# timer_rele.net
KiCad netlist of a schematic drawn in EAGLE
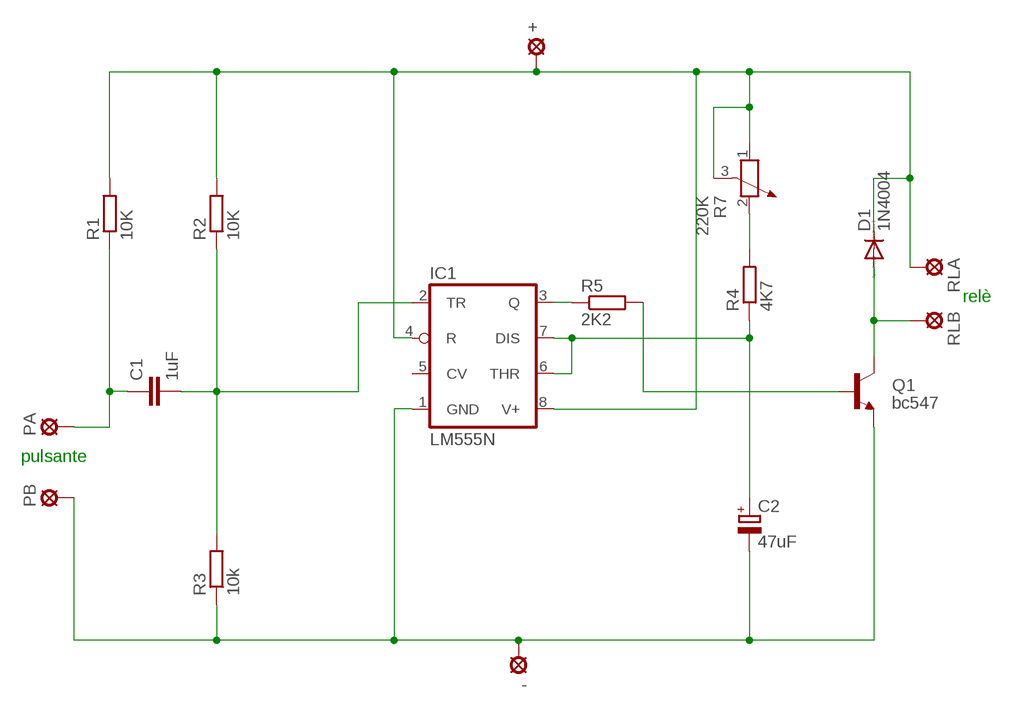
[diagram p0: schematic, sheet 1]

(export (version "E")
  (design (tool "Eeschema 10.0.6"))
  (components
    (comp (ref "+")
      (value "LSP10")
      (footprint "eagle-import:LSP10")
      (libsource (lib "eagle-import") (part "LSP10"))
    )
    (comp (ref "-")
      (value "LSP10")
      (footprint "eagle-import:LSP10")
      (libsource (lib "eagle-import") (part "LSP10"))
    )
    (comp (ref "C1")
      (value "1uF")
      (footprint "eagle-import:C050-030X075")
      (libsource (lib "eagle-import") (part "C-EU050-030X075"))
    )
    (comp (ref "C2")
      (value "47uF")
      (footprint "eagle-import:E2-5")
      (libsource (lib "eagle-import") (part "CPOL-EUE2-5"))
    )
    (comp (ref "D1")
      (value "1N4004")
      (footprint "eagle-import:DO41-10")
      (libsource (lib "eagle-import") (part "1N4004"))
    )
    (comp (ref "IC1")
      (value "LM555N")
      (footprint "eagle-import:DIL08")
      (libsource (lib "eagle-import") (part "555NLM"))
    )
    (comp (ref "PA")
      (value "LSP10")
      (footprint "eagle-import:LSP10")
      (libsource (lib "eagle-import") (part "LSP10"))
    )
    (comp (ref "PB")
      (value "LSP10")
      (footprint "eagle-import:LSP10")
      (libsource (lib "eagle-import") (part "LSP10"))
    )
    (comp (ref "Q1")
      (value "bc547")
      (footprint "eagle-import:TO-92-AMMO")
      (libsource (lib "eagle-import") (part "TRANSISTOR_NPNBC547"))
    )
    (comp (ref "R1")
      (value "10K")
      (footprint "eagle-import:0207_10")
      (libsource (lib "eagle-import") (part "R-EU_0207/10"))
    )
    (comp (ref "R2")
      (value "10K")
      (footprint "eagle-import:0207_10")
      (libsource (lib "eagle-import") (part "R-EU_0207/10"))
    )
    (comp (ref "R3")
      (value "10k")
      (footprint "eagle-import:0207_10")
      (libsource (lib "eagle-import") (part "R-EU_0207/10"))
    )
    (comp (ref "R4")
      (value "4K7")
      (footprint "eagle-import:0207_10")
      (libsource (lib "eagle-import") (part "R-EU_0207/10"))
    )
    (comp (ref "R5")
      (value "2K2")
      (footprint "eagle-import:0207_10")
      (libsource (lib "eagle-import") (part "R-EU_0207/10"))
    )
    (comp (ref "R7")
      (value "220K")
      (footprint "eagle-import:PT-10")
      (libsource (lib "eagle-import") (part "POTENTIOMETER_PT-10"))
    )
    (comp (ref "RLA")
      (value "LSP10")
      (footprint "eagle-import:LSP10")
      (libsource (lib "eagle-import") (part "LSP10"))
    )
    (comp (ref "RLB")
      (value "LSP10")
      (footprint "eagle-import:LSP10")
      (libsource (lib "eagle-import") (part "LSP10"))
    )
  )
  (nets
    (net (code "1") (name "Net-(C1-Pad1)") (class "Default")
      (node (ref "C1") (pin "1") (pinfunction "1_1") (pintype "passive"))
      (node (ref "PA") (pin "MP") (pinfunction "MP_MP") (pintype "passive"))
      (node (ref "R1") (pin "1") (pinfunction "1_1") (pintype "passive"))
    )
    (net (code "2") (name "Net-(IC1-DIS)") (class "Default")
      (node (ref "C2") (pin "+") (pinfunction "+_+") (pintype "passive"))
      (node (ref "IC1") (pin "6") (pinfunction "THR_6") (pintype "input"))
      (node (ref "IC1") (pin "7") (pinfunction "DIS_7") (pintype "input"))
      (node (ref "R4") (pin "1") (pinfunction "1_1") (pintype "passive"))
    )
    (net (code "3") (name "Net-(IC1-GND)") (class "Default")
      (node (ref "-") (pin "MP") (pinfunction "MP_MP") (pintype "passive"))
      (node (ref "C2") (pin "-") (pinfunction "-_-") (pintype "passive"))
      (node (ref "IC1") (pin "1") (pinfunction "GND_1") (pintype "power_in"))
      (node (ref "PB") (pin "MP") (pinfunction "MP_MP") (pintype "passive"))
      (node (ref "Q1") (pin "3") (pinfunction "E_3") (pintype "passive"))
      (node (ref "R3") (pin "1") (pinfunction "1_1") (pintype "passive"))
    )
    (net (code "4") (name "Net-(IC1-Q)") (class "Default")
      (node (ref "IC1") (pin "3") (pinfunction "Q_3") (pintype "output"))
      (node (ref "R5") (pin "1") (pinfunction "1_1") (pintype "passive"))
    )
    (net (code "5") (name "Net-(IC1-R)") (class "Default")
      (node (ref "+") (pin "MP") (pinfunction "MP_MP") (pintype "passive"))
      (node (ref "D1") (pin "C") (pinfunction "C_C") (pintype "passive"))
      (node (ref "IC1") (pin "4") (pinfunction "R_4") (pintype "input"))
      (node (ref "IC1") (pin "8") (pinfunction "V+_8") (pintype "power_in"))
      (node (ref "R1") (pin "2") (pinfunction "2_2") (pintype "passive"))
      (node (ref "R2") (pin "2") (pinfunction "2_2") (pintype "passive"))
      (node (ref "R7") (pin "1") (pinfunction "1_1") (pintype "passive"))
      (node (ref "R7") (pin "3") (pinfunction "3_3") (pintype "passive"))
      (node (ref "RLA") (pin "MP") (pinfunction "MP_MP") (pintype "passive"))
    )
    (net (code "6") (name "Net-(IC1-TR)") (class "Default")
      (node (ref "C1") (pin "2") (pinfunction "2_2") (pintype "passive"))
      (node (ref "IC1") (pin "2") (pinfunction "TR_2") (pintype "input"))
      (node (ref "R2") (pin "1") (pinfunction "1_1") (pintype "passive"))
      (node (ref "R3") (pin "2") (pinfunction "2_2") (pintype "passive"))
    )
    (net (code "7") (name "Net-(Q1-B)") (class "Default")
      (node (ref "Q1") (pin "2") (pinfunction "B_2") (pintype "passive"))
      (node (ref "R5") (pin "2") (pinfunction "2_2") (pintype "passive"))
    )
    (net (code "8") (name "Net-(Q1-C)") (class "Default")
      (node (ref "D1") (pin "A") (pinfunction "A_A") (pintype "passive"))
      (node (ref "Q1") (pin "1") (pinfunction "C_1") (pintype "passive"))
      (node (ref "RLB") (pin "MP") (pinfunction "MP_MP") (pintype "passive"))
    )
    (net (code "9") (name "Net-(R4-Pad2)") (class "Default")
      (node (ref "R4") (pin "2") (pinfunction "2_2") (pintype "passive"))
      (node (ref "R7") (pin "2") (pinfunction "2_2") (pintype "passive"))
    )
    (net (code "10") (name "unconnected-(IC1-CV-Pad5)") (class "Default")
      (node (ref "IC1") (pin "5") (pinfunction "CV_5") (pintype "input"))
    )
  )
)
